# Top_Board.net
KiCad netlist of a schematic drawn in Altium Designer
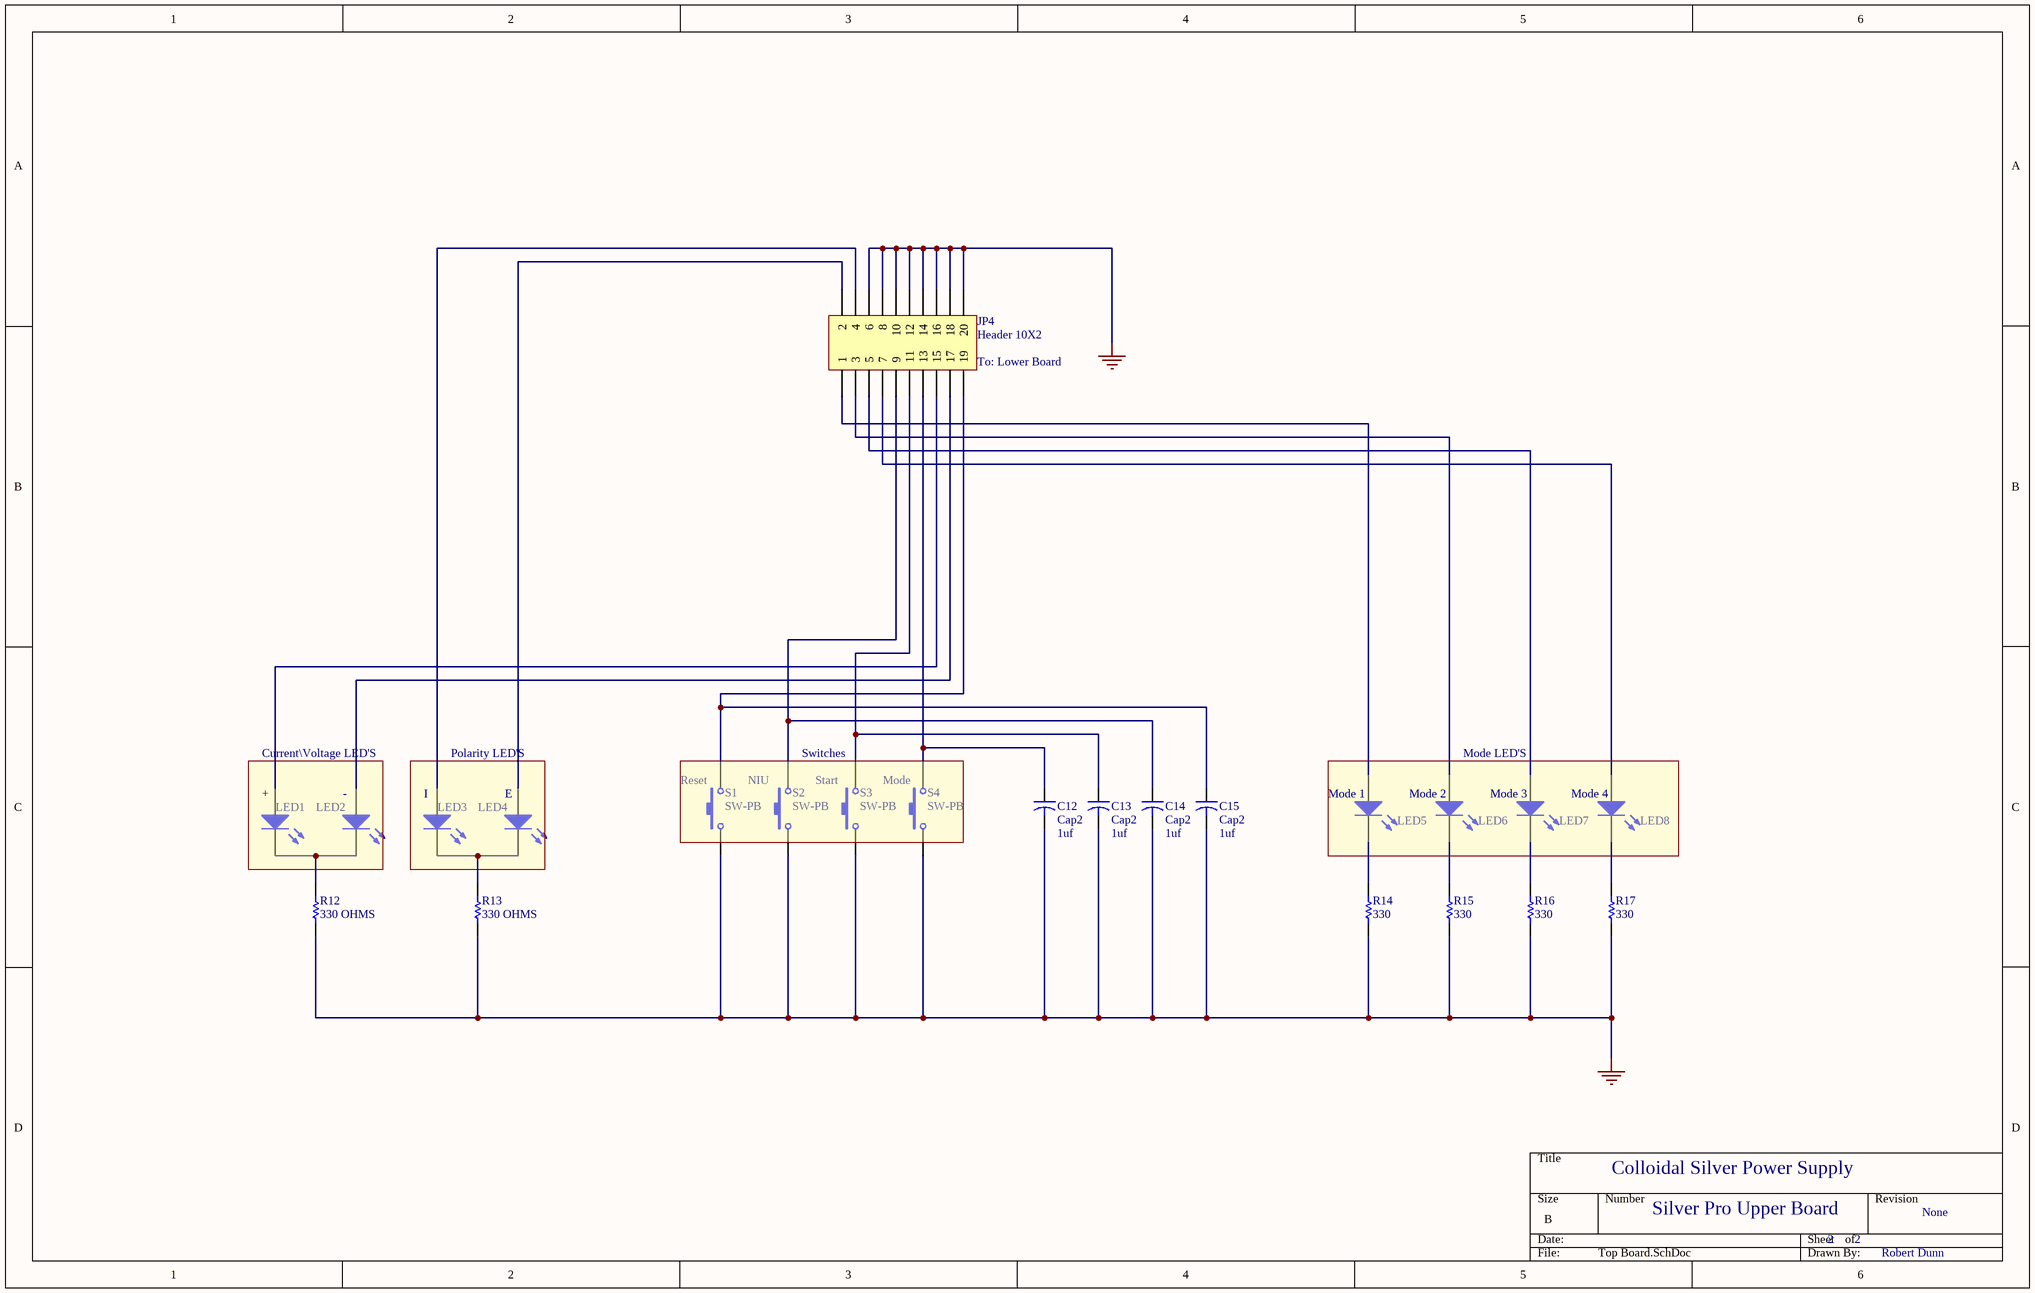
[diagram p0: Top Board.SchDoc]

(export (version "E")
  (design (tool "Eeschema 10.0.6"))
  (components
    (comp (ref "C12")
      (value "Cap2")
      (footprint "CAPR5-4X5")
      (description "Capacitor")
      (fields (field (name "ALTIUM_VALUE") "1uf") (field (name "PUBLISHER") "Altium Limited"))
      (libsource (lib "Miscellaneous Devices") (part "Cap2"))
    )
    (comp (ref "C13")
      (value "Cap2")
      (footprint "CAPR5-4X5")
      (description "Capacitor")
      (fields (field (name "ALTIUM_VALUE") "1uf") (field (name "PUBLISHER") "Altium Limited"))
      (libsource (lib "Miscellaneous Devices") (part "Cap2"))
    )
    (comp (ref "C14")
      (value "Cap2")
      (footprint "CAPR5-4X5")
      (description "Capacitor")
      (fields (field (name "ALTIUM_VALUE") "1uf") (field (name "PUBLISHER") "Altium Limited"))
      (libsource (lib "Miscellaneous Devices") (part "Cap2"))
    )
    (comp (ref "C15")
      (value "Cap2")
      (footprint "CAPR5-4X5")
      (description "Capacitor")
      (fields (field (name "ALTIUM_VALUE") "1uf") (field (name "PUBLISHER") "Altium Limited"))
      (libsource (lib "Miscellaneous Devices") (part "Cap2"))
    )
    (comp (ref "DS1")
      (value "LED1")
      (footprint "LED-1")
      (description "Typical RED GaAs LED")
      (fields (field (name "PUBLISHER") "Altium Limited"))
      (libsource (lib "Miscellaneous Devices") (part "LED1"))
    )
    (comp (ref "DS2")
      (value "LED2")
      (footprint "LED-1")
      (description "Typical RED GaAs LED")
      (fields (field (name "PUBLISHER") "Altium Limited"))
      (libsource (lib "Miscellaneous Devices") (part "LED1"))
    )
    (comp (ref "DS3")
      (value "LED3")
      (footprint "LED-1")
      (description "Typical RED GaAs LED")
      (fields (field (name "PUBLISHER") "Altium Limited"))
      (libsource (lib "Miscellaneous Devices") (part "LED1"))
    )
    (comp (ref "DS4")
      (value "LED4")
      (footprint "LED-1")
      (description "Typical RED GaAs LED")
      (fields (field (name "PUBLISHER") "Altium Limited"))
      (libsource (lib "Miscellaneous Devices") (part "LED1"))
    )
    (comp (ref "DS5")
      (value "LED5")
      (footprint "LED-1")
      (description "Typical RED GaAs LED")
      (fields (field (name "PUBLISHER") "Altium Limited"))
      (libsource (lib "Miscellaneous Devices") (part "LED1"))
    )
    (comp (ref "DS6")
      (value "LED6")
      (footprint "LED-1")
      (description "Typical RED GaAs LED")
      (fields (field (name "PUBLISHER") "Altium Limited"))
      (libsource (lib "Miscellaneous Devices") (part "LED1"))
    )
    (comp (ref "DS7")
      (value "LED7")
      (footprint "LED-1")
      (description "Typical RED GaAs LED")
      (fields (field (name "PUBLISHER") "Altium Limited"))
      (libsource (lib "Miscellaneous Devices") (part "LED1"))
    )
    (comp (ref "DS8")
      (value "LED8")
      (footprint "LED-1")
      (description "Typical RED GaAs LED")
      (fields (field (name "PUBLISHER") "Altium Limited"))
      (libsource (lib "Miscellaneous Devices") (part "LED1"))
    )
    (comp (ref "JP4")
      (value "Header 10X2")
      (footprint "HDR2X10")
      (description "Header, 10-Pin, Dual row")
      (fields (field (name "PUBLISHER") "Altium Limited"))
      (libsource (lib "Miscellaneous Connectors") (part "Header 10X2"))
    )
    (comp (ref "R12")
      (value "330 OHMS")
      (footprint "AXIAL-0.3")
      (description "Resistor")
      (fields (field (name "Comment") "Res1") (field (name "PUBLISHER") "Altium Limited"))
      (libsource (lib "Miscellaneous Devices") (part "Res1"))
    )
    (comp (ref "R13")
      (value "330 OHMS")
      (footprint "AXIAL-0.3")
      (description "Resistor")
      (fields (field (name "Comment") "Res1") (field (name "PUBLISHER") "Altium Limited"))
      (libsource (lib "Miscellaneous Devices") (part "Res1"))
    )
    (comp (ref "R14")
      (value "330")
      (footprint "AXIAL-0.3")
      (description "Resistor")
      (fields (field (name "Comment") "Res1") (field (name "PUBLISHER") "Altium Limited"))
      (libsource (lib "Miscellaneous Devices") (part "Res1"))
    )
    (comp (ref "R15")
      (value "330")
      (footprint "AXIAL-0.3")
      (description "Resistor")
      (fields (field (name "Comment") "Res1") (field (name "PUBLISHER") "Altium Limited"))
      (libsource (lib "Miscellaneous Devices") (part "Res1"))
    )
    (comp (ref "R16")
      (value "330")
      (footprint "AXIAL-0.3")
      (description "Resistor")
      (fields (field (name "Comment") "Res1") (field (name "PUBLISHER") "Altium Limited"))
      (libsource (lib "Miscellaneous Devices") (part "Res1"))
    )
    (comp (ref "R17")
      (value "330")
      (footprint "AXIAL-0.3")
      (description "Resistor")
      (fields (field (name "Comment") "Res1") (field (name "PUBLISHER") "Altium Limited"))
      (libsource (lib "Miscellaneous Devices") (part "Res1"))
    )
    (comp (ref "S1")
      (value "SW-PB")
      (footprint "SPST-2")
      (description "Switch")
      (fields (field (name "PUBLISHER") "Altium Limited"))
      (libsource (lib "Miscellaneous Devices") (part "SW-PB"))
    )
    (comp (ref "S2")
      (value "SW-PB")
      (footprint "SPST-2")
      (description "Switch")
      (fields (field (name "PUBLISHER") "Altium Limited"))
      (libsource (lib "Miscellaneous Devices") (part "SW-PB"))
    )
    (comp (ref "S3")
      (value "SW-PB")
      (footprint "SPST-2")
      (description "Switch")
      (fields (field (name "PUBLISHER") "Altium Limited"))
      (libsource (lib "Miscellaneous Devices") (part "SW-PB"))
    )
    (comp (ref "S4")
      (value "SW-PB")
      (footprint "SPST-2")
      (description "Switch")
      (fields (field (name "PUBLISHER") "Altium Limited"))
      (libsource (lib "Miscellaneous Devices") (part "SW-PB"))
    )
  )
  (nets
    (net (code "1") (name "GND") (class "Default")
      (node (ref "C12") (pin "2") (pinfunction "2_2") (pintype "passive"))
      (node (ref "C13") (pin "2") (pinfunction "2_2") (pintype "passive"))
      (node (ref "C14") (pin "2") (pinfunction "2_2") (pintype "passive"))
      (node (ref "C15") (pin "2") (pinfunction "2_2") (pintype "passive"))
      (node (ref "JP4") (pin "10") (pinfunction "10_10") (pintype "passive"))
      (node (ref "JP4") (pin "12") (pinfunction "12_12") (pintype "passive"))
      (node (ref "JP4") (pin "14") (pinfunction "14_14") (pintype "passive"))
      (node (ref "JP4") (pin "16") (pinfunction "16_16") (pintype "passive"))
      (node (ref "JP4") (pin "18") (pinfunction "18_18") (pintype "passive"))
      (node (ref "JP4") (pin "20") (pinfunction "20_20") (pintype "passive"))
      (node (ref "JP4") (pin "6") (pinfunction "6_6") (pintype "passive"))
      (node (ref "JP4") (pin "8") (pinfunction "8_8") (pintype "passive"))
      (node (ref "R12") (pin "1") (pinfunction "1_1") (pintype "passive"))
      (node (ref "R13") (pin "1") (pinfunction "1_1") (pintype "passive"))
      (node (ref "R14") (pin "1") (pinfunction "1_1") (pintype "passive"))
      (node (ref "R15") (pin "1") (pinfunction "1_1") (pintype "passive"))
      (node (ref "R16") (pin "1") (pinfunction "1_1") (pintype "passive"))
      (node (ref "R17") (pin "1") (pinfunction "1_1") (pintype "passive"))
      (node (ref "S1") (pin "1") (pinfunction "1_1") (pintype "passive"))
      (node (ref "S2") (pin "1") (pinfunction "1_1") (pintype "passive"))
      (node (ref "S3") (pin "1") (pinfunction "1_1") (pintype "passive"))
      (node (ref "S4") (pin "1") (pinfunction "1_1") (pintype "passive"))
    )
    (net (code "2") (name "Net-(C12-Pad1)") (class "Default")
      (node (ref "C12") (pin "1") (pinfunction "1_1") (pintype "passive"))
      (node (ref "JP4") (pin "13") (pinfunction "13_13") (pintype "passive"))
      (node (ref "S4") (pin "2") (pinfunction "2_2") (pintype "passive"))
    )
    (net (code "3") (name "Net-(C13-Pad1)") (class "Default")
      (node (ref "C13") (pin "1") (pinfunction "1_1") (pintype "passive"))
      (node (ref "JP4") (pin "11") (pinfunction "11_11") (pintype "passive"))
      (node (ref "S3") (pin "2") (pinfunction "2_2") (pintype "passive"))
    )
    (net (code "4") (name "Net-(C14-Pad1)") (class "Default")
      (node (ref "C14") (pin "1") (pinfunction "1_1") (pintype "passive"))
      (node (ref "JP4") (pin "9") (pinfunction "9_9") (pintype "passive"))
      (node (ref "S2") (pin "2") (pinfunction "2_2") (pintype "passive"))
    )
    (net (code "5") (name "Net-(C15-Pad1)") (class "Default")
      (node (ref "C15") (pin "1") (pinfunction "1_1") (pintype "passive"))
      (node (ref "JP4") (pin "19") (pinfunction "19_19") (pintype "passive"))
      (node (ref "S1") (pin "2") (pinfunction "2_2") (pintype "passive"))
    )
    (net (code "6") (name "Net-(DS1-A)") (class "Default")
      (node (ref "DS1") (pin "1") (pinfunction "A_1") (pintype "passive"))
      (node (ref "JP4") (pin "15") (pinfunction "15_15") (pintype "passive"))
    )
    (net (code "7") (name "Net-(DS1-K)") (class "Default")
      (node (ref "DS1") (pin "2") (pinfunction "K_2") (pintype "passive"))
      (node (ref "DS2") (pin "2") (pinfunction "K_2") (pintype "passive"))
      (node (ref "R12") (pin "2") (pinfunction "2_2") (pintype "passive"))
    )
    (net (code "8") (name "Net-(DS2-A)") (class "Default")
      (node (ref "DS2") (pin "1") (pinfunction "A_1") (pintype "passive"))
      (node (ref "JP4") (pin "17") (pinfunction "17_17") (pintype "passive"))
    )
    (net (code "9") (name "Net-(DS3-A)") (class "Default")
      (node (ref "DS3") (pin "1") (pinfunction "A_1") (pintype "passive"))
      (node (ref "JP4") (pin "4") (pinfunction "4_4") (pintype "passive"))
    )
    (net (code "10") (name "Net-(DS3-K)") (class "Default")
      (node (ref "DS3") (pin "2") (pinfunction "K_2") (pintype "passive"))
      (node (ref "DS4") (pin "2") (pinfunction "K_2") (pintype "passive"))
      (node (ref "R13") (pin "2") (pinfunction "2_2") (pintype "passive"))
    )
    (net (code "11") (name "Net-(DS4-A)") (class "Default")
      (node (ref "DS4") (pin "1") (pinfunction "A_1") (pintype "passive"))
      (node (ref "JP4") (pin "2") (pinfunction "2_2") (pintype "passive"))
    )
    (net (code "12") (name "Net-(DS5-A)") (class "Default")
      (node (ref "DS5") (pin "1") (pinfunction "A_1") (pintype "passive"))
      (node (ref "JP4") (pin "1") (pinfunction "1_1") (pintype "passive"))
    )
    (net (code "13") (name "Net-(DS5-K)") (class "Default")
      (node (ref "DS5") (pin "2") (pinfunction "K_2") (pintype "passive"))
      (node (ref "R14") (pin "2") (pinfunction "2_2") (pintype "passive"))
    )
    (net (code "14") (name "Net-(DS6-A)") (class "Default")
      (node (ref "DS6") (pin "1") (pinfunction "A_1") (pintype "passive"))
      (node (ref "JP4") (pin "3") (pinfunction "3_3") (pintype "passive"))
    )
    (net (code "15") (name "Net-(DS6-K)") (class "Default")
      (node (ref "DS6") (pin "2") (pinfunction "K_2") (pintype "passive"))
      (node (ref "R15") (pin "2") (pinfunction "2_2") (pintype "passive"))
    )
    (net (code "16") (name "Net-(DS7-A)") (class "Default")
      (node (ref "DS7") (pin "1") (pinfunction "A_1") (pintype "passive"))
      (node (ref "JP4") (pin "5") (pinfunction "5_5") (pintype "passive"))
    )
    (net (code "17") (name "Net-(DS7-K)") (class "Default")
      (node (ref "DS7") (pin "2") (pinfunction "K_2") (pintype "passive"))
      (node (ref "R16") (pin "2") (pinfunction "2_2") (pintype "passive"))
    )
    (net (code "18") (name "Net-(DS8-A)") (class "Default")
      (node (ref "DS8") (pin "1") (pinfunction "A_1") (pintype "passive"))
      (node (ref "JP4") (pin "7") (pinfunction "7_7") (pintype "passive"))
    )
    (net (code "19") (name "Net-(DS8-K)") (class "Default")
      (node (ref "DS8") (pin "2") (pinfunction "K_2") (pintype "passive"))
      (node (ref "R17") (pin "2") (pinfunction "2_2") (pintype "passive"))
    )
  )
)
